# mixiple.net
KiCad netlist of a schematic drawn in EAGLE
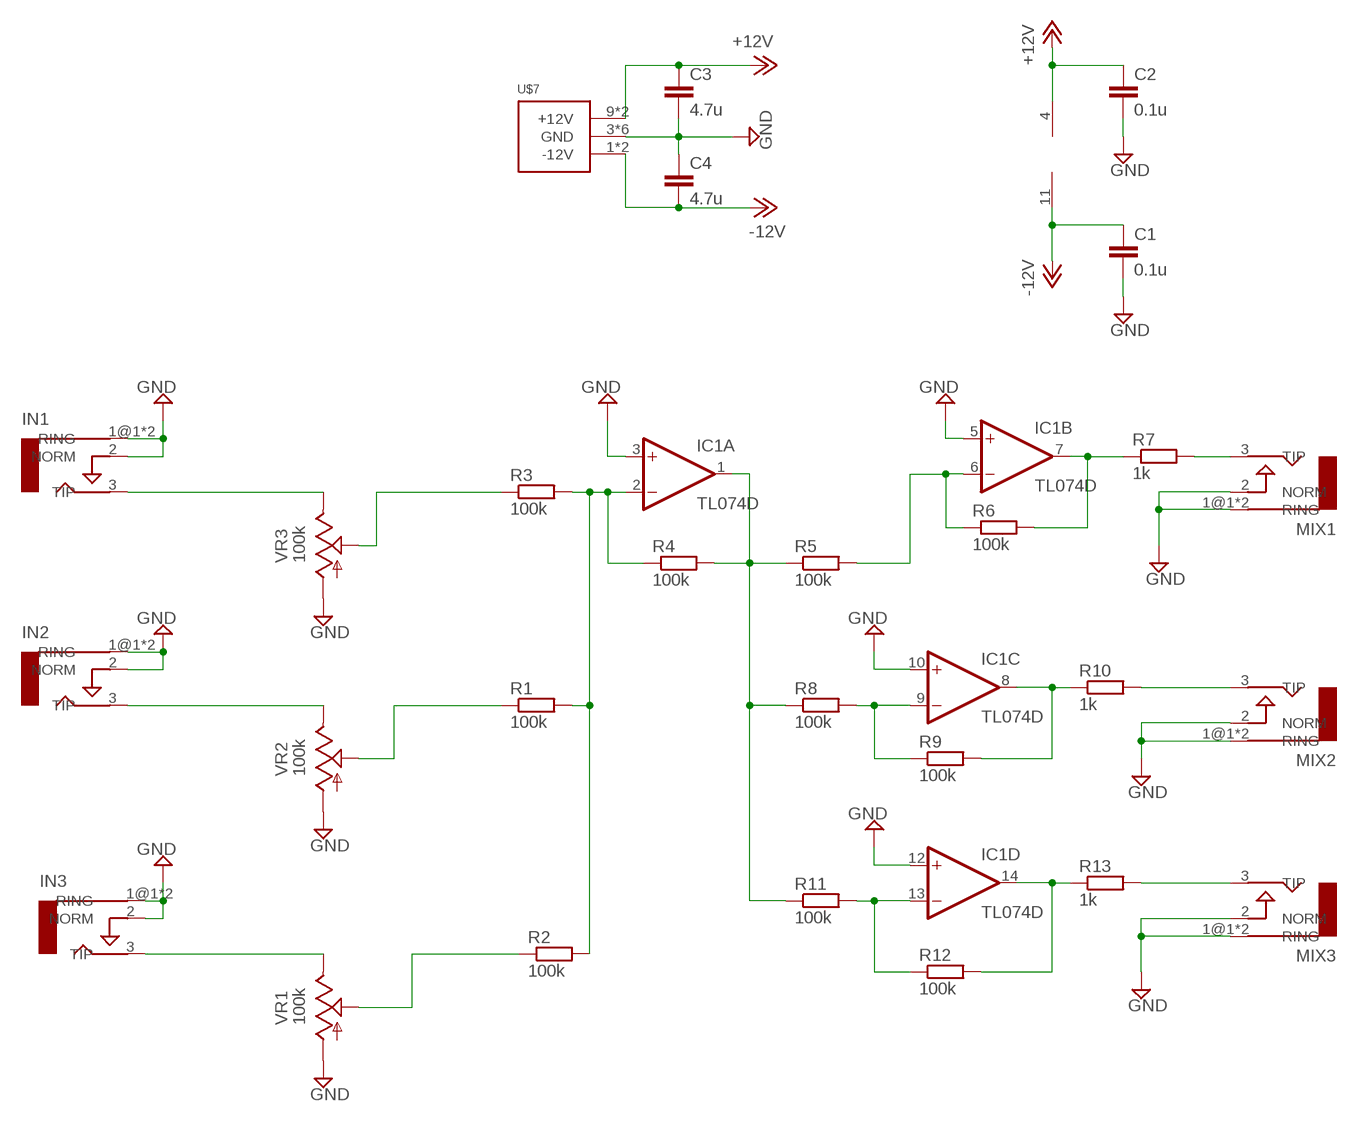
[diagram p0: schematic, sheet 1]

(export (version "E")
  (design (tool "Eeschema 10.0.6"))
  (components
    (comp (ref "C1")
      (value "0.1u")
      (footprint "eagle-import:C0805")
      (libsource (lib "eagle-import") (part "C-EUC0805"))
    )
    (comp (ref "C2")
      (value "0.1u")
      (footprint "eagle-import:C0805")
      (libsource (lib "eagle-import") (part "C-EUC0805"))
    )
    (comp (ref "C3")
      (value "4.7u")
      (footprint "eagle-import:C0805")
      (libsource (lib "eagle-import") (part "C-EUC0805"))
    )
    (comp (ref "C4")
      (value "4.7u")
      (footprint "eagle-import:C0805")
      (libsource (lib "eagle-import") (part "C-EUC0805"))
    )
    (comp (ref "IC1")
      (value "TL074D")
      (footprint "eagle-import:SO14")
      (libsource (lib "eagle-import") (part "TL074D"))
    )
    (comp (ref "IN1")
      (value "AUDIO-JACKERTHENVAR")
      (footprint "eagle-import:ERTHENVAR-JACK")
      (libsource (lib "eagle-import") (part "AUDIO-JACKERTHENVAR"))
    )
    (comp (ref "IN2")
      (value "AUDIO-JACKERTHENVAR")
      (footprint "eagle-import:ERTHENVAR-JACK")
      (libsource (lib "eagle-import") (part "AUDIO-JACKERTHENVAR"))
    )
    (comp (ref "IN3")
      (value "AUDIO-JACKERTHENVAR")
      (footprint "eagle-import:ERTHENVAR-JACK")
      (libsource (lib "eagle-import") (part "AUDIO-JACKERTHENVAR"))
    )
    (comp (ref "MIX1")
      (value "AUDIO-JACKERTHENVAR")
      (footprint "eagle-import:ERTHENVAR-JACK")
      (libsource (lib "eagle-import") (part "AUDIO-JACKERTHENVAR"))
    )
    (comp (ref "MIX2")
      (value "AUDIO-JACKERTHENVAR")
      (footprint "eagle-import:ERTHENVAR-JACK")
      (libsource (lib "eagle-import") (part "AUDIO-JACKERTHENVAR"))
    )
    (comp (ref "MIX3")
      (value "AUDIO-JACKERTHENVAR")
      (footprint "eagle-import:ERTHENVAR-JACK")
      (libsource (lib "eagle-import") (part "AUDIO-JACKERTHENVAR"))
    )
    (comp (ref "R1")
      (value "100k")
      (footprint "eagle-import:R0805")
      (libsource (lib "eagle-import") (part "R-EU_R0805"))
    )
    (comp (ref "R2")
      (value "100k")
      (footprint "eagle-import:R0805")
      (libsource (lib "eagle-import") (part "R-EU_R0805"))
    )
    (comp (ref "R3")
      (value "100k")
      (footprint "eagle-import:R0805")
      (libsource (lib "eagle-import") (part "R-EU_R0805"))
    )
    (comp (ref "R4")
      (value "100k")
      (footprint "eagle-import:R0805")
      (libsource (lib "eagle-import") (part "R-EU_R0805"))
    )
    (comp (ref "R5")
      (value "100k")
      (footprint "eagle-import:R0805")
      (libsource (lib "eagle-import") (part "R-EU_R0805"))
    )
    (comp (ref "R6")
      (value "100k")
      (footprint "eagle-import:R0805")
      (libsource (lib "eagle-import") (part "R-EU_R0805"))
    )
    (comp (ref "R7")
      (value "1k")
      (footprint "eagle-import:R0805")
      (libsource (lib "eagle-import") (part "R-EU_R0805"))
    )
    (comp (ref "R8")
      (value "100k")
      (footprint "eagle-import:R0805")
      (libsource (lib "eagle-import") (part "R-EU_R0805"))
    )
    (comp (ref "R9")
      (value "100k")
      (footprint "eagle-import:R0805")
      (libsource (lib "eagle-import") (part "R-EU_R0805"))
    )
    (comp (ref "R10")
      (value "1k")
      (footprint "eagle-import:R0805")
      (libsource (lib "eagle-import") (part "R-EU_R0805"))
    )
    (comp (ref "R11")
      (value "100k")
      (footprint "eagle-import:R0805")
      (libsource (lib "eagle-import") (part "R-EU_R0805"))
    )
    (comp (ref "R12")
      (value "100k")
      (footprint "eagle-import:R0805")
      (libsource (lib "eagle-import") (part "R-EU_R0805"))
    )
    (comp (ref "R13")
      (value "1k")
      (footprint "eagle-import:R0805")
      (libsource (lib "eagle-import") (part "R-EU_R0805"))
    )
    (comp (ref "U$7")
      (value "POWER_SIMPLE10")
      (footprint "eagle-import:POWER_10")
      (libsource (lib "eagle-import") (part "POWER_SIMPLE10"))
    )
    (comp (ref "VR1")
      (value "100k")
      (footprint "eagle-import:9MM_SNAP-IN_POT")
      (libsource (lib "eagle-import") (part "9MM_SNAP-IN_POT_"))
    )
    (comp (ref "VR2")
      (value "100k")
      (footprint "eagle-import:9MM_SNAP-IN_POT")
      (libsource (lib "eagle-import") (part "9MM_SNAP-IN_POT_"))
    )
    (comp (ref "VR3")
      (value "100k")
      (footprint "eagle-import:9MM_SNAP-IN_POT")
      (libsource (lib "eagle-import") (part "9MM_SNAP-IN_POT_"))
    )
  )
  (nets
    (net (code "1") (name "+12V") (class "Default")
      (node (ref "C2") (pin "1") (pinfunction "1_1") (pintype "passive"))
      (node (ref "C3") (pin "1") (pinfunction "1_1") (pintype "passive"))
      (node (ref "IC1") (pin "4") (pinfunction "V+_4") (pintype "power_in"))
      (node (ref "U$7") (pin "10") (pinfunction "+12V_10") (pintype "bidirectional"))
      (node (ref "U$7") (pin "9") (pinfunction "+12V_9") (pintype "bidirectional"))
    )
    (net (code "2") (name "-12V") (class "Default")
      (node (ref "C1") (pin "1") (pinfunction "1_1") (pintype "passive"))
      (node (ref "C4") (pin "2") (pinfunction "2_2") (pintype "passive"))
      (node (ref "IC1") (pin "11") (pinfunction "V-_11") (pintype "power_in"))
      (node (ref "U$7") (pin "1") (pinfunction "-12V_1") (pintype "bidirectional"))
      (node (ref "U$7") (pin "2") (pinfunction "-12V_2") (pintype "bidirectional"))
    )
    (net (code "3") (name "GND") (class "Default")
      (node (ref "C1") (pin "2") (pinfunction "2_2") (pintype "passive"))
      (node (ref "C2") (pin "2") (pinfunction "2_2") (pintype "passive"))
      (node (ref "C3") (pin "2") (pinfunction "2_2") (pintype "passive"))
      (node (ref "C4") (pin "1") (pinfunction "1_1") (pintype "passive"))
      (node (ref "IC1") (pin "10") (pinfunction "+IN_10") (pintype "input"))
      (node (ref "IC1") (pin "12") (pinfunction "+IN_12") (pintype "input"))
      (node (ref "IC1") (pin "3") (pinfunction "+IN_3") (pintype "input"))
      (node (ref "IC1") (pin "5") (pinfunction "+IN_5") (pintype "input"))
      (node (ref "IN1") (pin "1@1") (pinfunction "RING_1@1") (pintype "bidirectional"))
      (node (ref "IN1") (pin "1@2") (pinfunction "RING_1@2") (pintype "bidirectional"))
      (node (ref "IN1") (pin "2") (pinfunction "NORM_2") (pintype "bidirectional"))
      (node (ref "IN2") (pin "1@1") (pinfunction "RING_1@1") (pintype "bidirectional"))
      (node (ref "IN2") (pin "1@2") (pinfunction "RING_1@2") (pintype "bidirectional"))
      (node (ref "IN2") (pin "2") (pinfunction "NORM_2") (pintype "bidirectional"))
      (node (ref "IN3") (pin "1@1") (pinfunction "RING_1@1") (pintype "bidirectional"))
      (node (ref "IN3") (pin "1@2") (pinfunction "RING_1@2") (pintype "bidirectional"))
      (node (ref "IN3") (pin "2") (pinfunction "NORM_2") (pintype "bidirectional"))
      (node (ref "MIX1") (pin "1@1") (pinfunction "RING_1@1") (pintype "bidirectional"))
      (node (ref "MIX1") (pin "1@2") (pinfunction "RING_1@2") (pintype "bidirectional"))
      (node (ref "MIX1") (pin "2") (pinfunction "NORM_2") (pintype "bidirectional"))
      (node (ref "MIX2") (pin "1@1") (pinfunction "RING_1@1") (pintype "bidirectional"))
      (node (ref "MIX2") (pin "1@2") (pinfunction "RING_1@2") (pintype "bidirectional"))
      (node (ref "MIX2") (pin "2") (pinfunction "NORM_2") (pintype "bidirectional"))
      (node (ref "MIX3") (pin "1@1") (pinfunction "RING_1@1") (pintype "bidirectional"))
      (node (ref "MIX3") (pin "1@2") (pinfunction "RING_1@2") (pintype "bidirectional"))
      (node (ref "MIX3") (pin "2") (pinfunction "NORM_2") (pintype "bidirectional"))
      (node (ref "U$7") (pin "3") (pinfunction "GND_3") (pintype "bidirectional"))
      (node (ref "U$7") (pin "4") (pinfunction "GND_4") (pintype "bidirectional"))
      (node (ref "U$7") (pin "5") (pinfunction "GND_5") (pintype "bidirectional"))
      (node (ref "U$7") (pin "6") (pinfunction "GND_6") (pintype "bidirectional"))
      (node (ref "U$7") (pin "7") (pinfunction "GND_7") (pintype "bidirectional"))
      (node (ref "U$7") (pin "8") (pinfunction "GND_8") (pintype "bidirectional"))
      (node (ref "VR1") (pin "1") (pinfunction "A_1") (pintype "passive"))
      (node (ref "VR2") (pin "1") (pinfunction "A_1") (pintype "passive"))
      (node (ref "VR3") (pin "1") (pinfunction "A_1") (pintype "passive"))
    )
    (net (code "4") (name "Net-(IC1A--IN)") (class "Default")
      (node (ref "IC1") (pin "2") (pinfunction "-IN_2") (pintype "input"))
      (node (ref "R1") (pin "2") (pinfunction "2_2") (pintype "passive"))
      (node (ref "R2") (pin "2") (pinfunction "2_2") (pintype "passive"))
      (node (ref "R3") (pin "2") (pinfunction "2_2") (pintype "passive"))
      (node (ref "R4") (pin "1") (pinfunction "1_1") (pintype "passive"))
    )
    (net (code "5") (name "Net-(IC1A-OUT)") (class "Default")
      (node (ref "IC1") (pin "1") (pinfunction "OUT_1") (pintype "output"))
      (node (ref "R11") (pin "1") (pinfunction "1_1") (pintype "passive"))
      (node (ref "R4") (pin "2") (pinfunction "2_2") (pintype "passive"))
      (node (ref "R5") (pin "1") (pinfunction "1_1") (pintype "passive"))
      (node (ref "R8") (pin "1") (pinfunction "1_1") (pintype "passive"))
    )
    (net (code "6") (name "Net-(IC1B--IN)") (class "Default")
      (node (ref "IC1") (pin "6") (pinfunction "-IN_6") (pintype "input"))
      (node (ref "R5") (pin "2") (pinfunction "2_2") (pintype "passive"))
      (node (ref "R6") (pin "1") (pinfunction "1_1") (pintype "passive"))
    )
    (net (code "7") (name "Net-(IC1B-OUT)") (class "Default")
      (node (ref "IC1") (pin "7") (pinfunction "OUT_7") (pintype "output"))
      (node (ref "R6") (pin "2") (pinfunction "2_2") (pintype "passive"))
      (node (ref "R7") (pin "1") (pinfunction "1_1") (pintype "passive"))
    )
    (net (code "8") (name "Net-(IC1C--IN)") (class "Default")
      (node (ref "IC1") (pin "9") (pinfunction "-IN_9") (pintype "input"))
      (node (ref "R8") (pin "2") (pinfunction "2_2") (pintype "passive"))
      (node (ref "R9") (pin "1") (pinfunction "1_1") (pintype "passive"))
    )
    (net (code "9") (name "Net-(IC1C-OUT)") (class "Default")
      (node (ref "IC1") (pin "8") (pinfunction "OUT_8") (pintype "output"))
      (node (ref "R10") (pin "1") (pinfunction "1_1") (pintype "passive"))
      (node (ref "R9") (pin "2") (pinfunction "2_2") (pintype "passive"))
    )
    (net (code "10") (name "Net-(IC1D--IN)") (class "Default")
      (node (ref "IC1") (pin "13") (pinfunction "-IN_13") (pintype "input"))
      (node (ref "R11") (pin "2") (pinfunction "2_2") (pintype "passive"))
      (node (ref "R12") (pin "1") (pinfunction "1_1") (pintype "passive"))
    )
    (net (code "11") (name "Net-(IC1D-OUT)") (class "Default")
      (node (ref "IC1") (pin "14") (pinfunction "OUT_14") (pintype "output"))
      (node (ref "R12") (pin "2") (pinfunction "2_2") (pintype "passive"))
      (node (ref "R13") (pin "1") (pinfunction "1_1") (pintype "passive"))
    )
    (net (code "12") (name "Net-(IN1-TIP)") (class "Default")
      (node (ref "IN1") (pin "3") (pinfunction "TIP_3") (pintype "bidirectional"))
      (node (ref "VR3") (pin "3") (pinfunction "E_3") (pintype "passive"))
    )
    (net (code "13") (name "Net-(IN2-TIP)") (class "Default")
      (node (ref "IN2") (pin "3") (pinfunction "TIP_3") (pintype "bidirectional"))
      (node (ref "VR2") (pin "3") (pinfunction "E_3") (pintype "passive"))
    )
    (net (code "14") (name "Net-(IN3-TIP)") (class "Default")
      (node (ref "IN3") (pin "3") (pinfunction "TIP_3") (pintype "bidirectional"))
      (node (ref "VR1") (pin "3") (pinfunction "E_3") (pintype "passive"))
    )
    (net (code "15") (name "Net-(MIX1-TIP)") (class "Default")
      (node (ref "MIX1") (pin "3") (pinfunction "TIP_3") (pintype "bidirectional"))
      (node (ref "R7") (pin "2") (pinfunction "2_2") (pintype "passive"))
    )
    (net (code "16") (name "Net-(MIX2-TIP)") (class "Default")
      (node (ref "MIX2") (pin "3") (pinfunction "TIP_3") (pintype "bidirectional"))
      (node (ref "R10") (pin "2") (pinfunction "2_2") (pintype "passive"))
    )
    (net (code "17") (name "Net-(MIX3-TIP)") (class "Default")
      (node (ref "MIX3") (pin "3") (pinfunction "TIP_3") (pintype "bidirectional"))
      (node (ref "R13") (pin "2") (pinfunction "2_2") (pintype "passive"))
    )
    (net (code "18") (name "Net-(VR1-S)") (class "Default")
      (node (ref "R2") (pin "1") (pinfunction "1_1") (pintype "passive"))
      (node (ref "VR1") (pin "2") (pinfunction "S_2") (pintype "passive"))
    )
    (net (code "19") (name "Net-(VR2-S)") (class "Default")
      (node (ref "R1") (pin "1") (pinfunction "1_1") (pintype "passive"))
      (node (ref "VR2") (pin "2") (pinfunction "S_2") (pintype "passive"))
    )
    (net (code "20") (name "Net-(VR3-S)") (class "Default")
      (node (ref "R3") (pin "1") (pinfunction "1_1") (pintype "passive"))
      (node (ref "VR3") (pin "2") (pinfunction "S_2") (pintype "passive"))
    )
  )
)
